# UDAWA_Gadadar.net
KiCad netlist of a schematic drawn in EAGLE
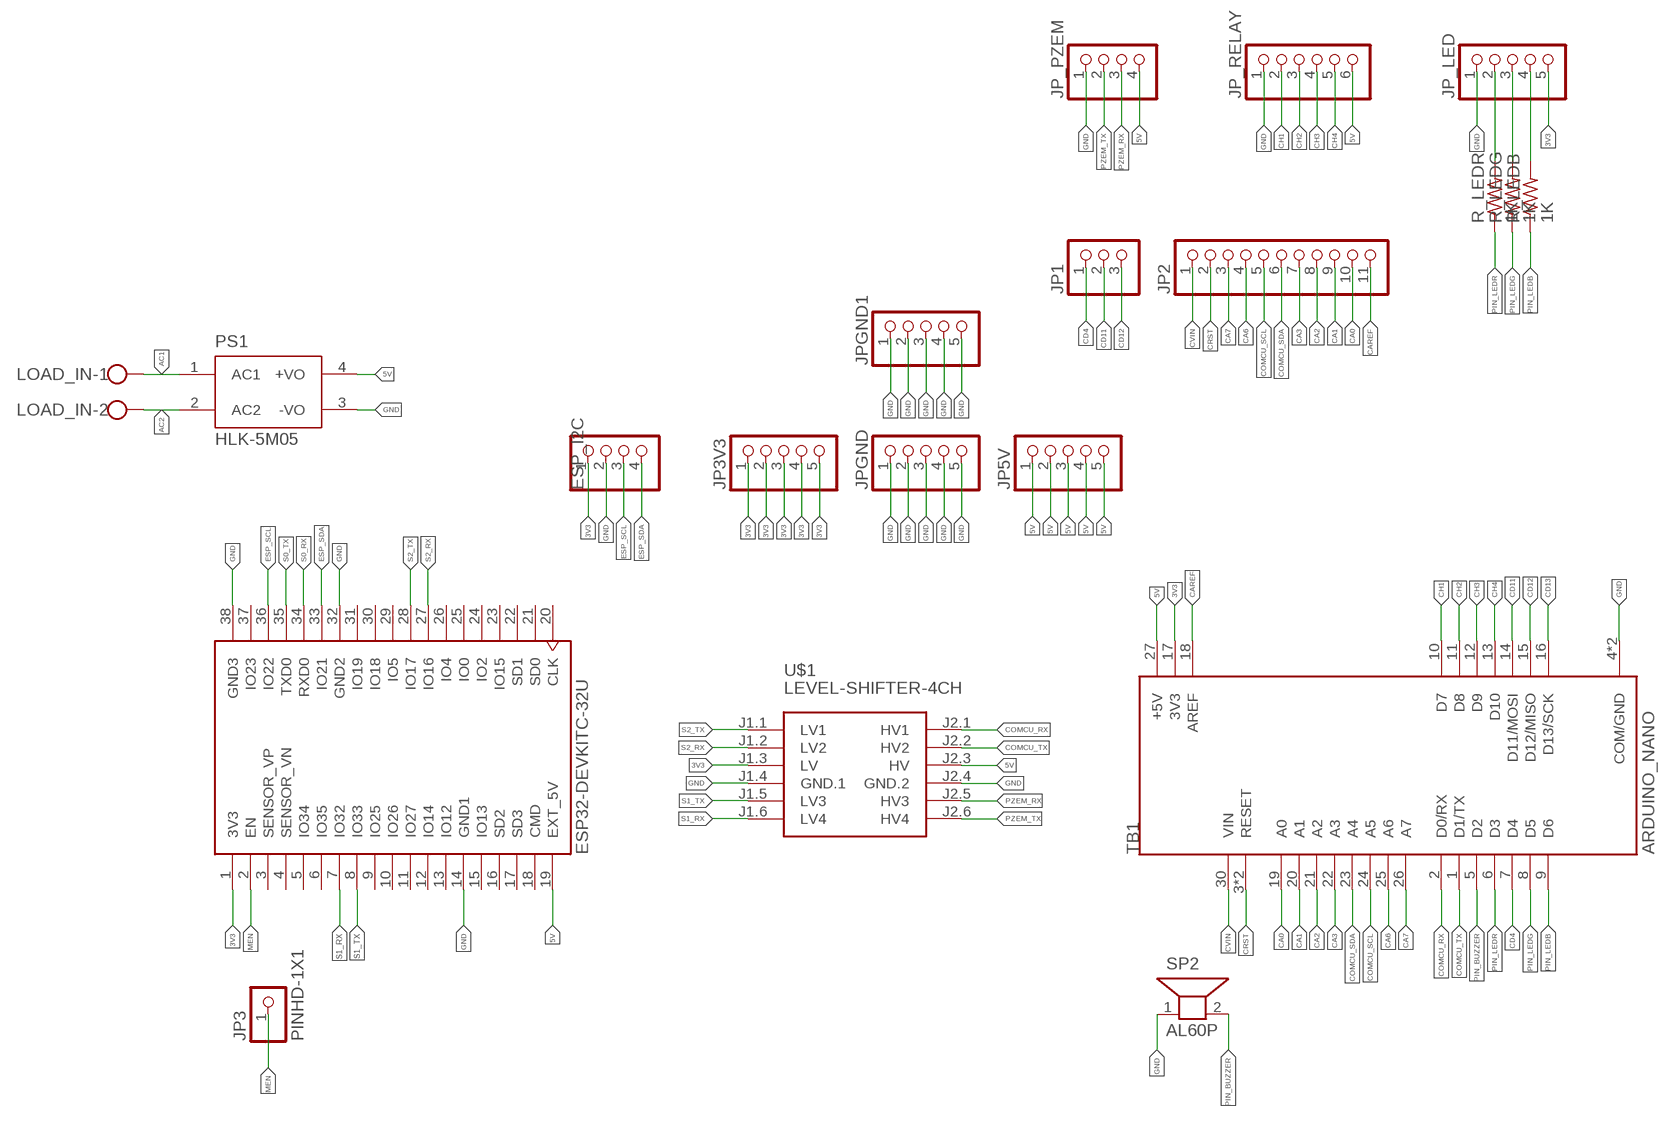
[diagram p0: schematic, sheet 1]

(export (version "E")
  (design (tool "Eeschema 10.0.6"))
  (components
    (comp (ref "ESP_I2C")
      (value "PINHD-1X4")
      (footprint "eagle-import:1X04")
      (libsource (lib "eagle-import") (part "PINHD-1X4"))
    )
    (comp (ref "JP1")
      (value "PINHD-1X3")
      (footprint "eagle-import:1X03")
      (libsource (lib "eagle-import") (part "PINHD-1X3"))
    )
    (comp (ref "JP2")
      (value "PINHD-1X11")
      (footprint "eagle-import:1X11")
      (libsource (lib "eagle-import") (part "PINHD-1X11"))
    )
    (comp (ref "JP3")
      (value "PINHD-1X1")
      (footprint "eagle-import:1X01")
      (libsource (lib "eagle-import") (part "PINHD-1X1"))
    )
    (comp (ref "JP3V3")
      (value "PINHD-1X5")
      (footprint "eagle-import:1X05")
      (libsource (lib "eagle-import") (part "PINHD-1X5"))
    )
    (comp (ref "JP5V")
      (value "PINHD-1X5")
      (footprint "eagle-import:1X05")
      (libsource (lib "eagle-import") (part "PINHD-1X5"))
    )
    (comp (ref "JPGND")
      (value "PINHD-1X5")
      (footprint "eagle-import:1X05")
      (libsource (lib "eagle-import") (part "PINHD-1X5"))
    )
    (comp (ref "JPGND1")
      (value "PINHD-1X5")
      (footprint "eagle-import:1X05")
      (libsource (lib "eagle-import") (part "PINHD-1X5"))
    )
    (comp (ref "JP_LED")
      (value "PINHD-1X5")
      (footprint "eagle-import:1X05")
      (libsource (lib "eagle-import") (part "PINHD-1X5"))
    )
    (comp (ref "JP_PZEM")
      (value "PINHD-1X4")
      (footprint "eagle-import:1X04")
      (libsource (lib "eagle-import") (part "PINHD-1X4"))
    )
    (comp (ref "JP_RELAY")
      (value "PINHD-1X6")
      (footprint "eagle-import:1X06")
      (libsource (lib "eagle-import") (part "PINHD-1X6"))
    )
    (comp (ref "LOAD_IN")
      (value "W237-102")
      (footprint "eagle-import:W237-102")
      (fields (field (name "MPN") "237-102"))
      (libsource (lib "eagle-import") (part "W237-102"))
    )
    (comp (ref "PS1")
      (value "HLK-5M05")
      (footprint "eagle-import:CONV_HLK-5M05")
      (fields (field (name "MF") "Hi-link"))
      (libsource (lib "eagle-import") (part "HLK-5M05"))
    )
    (comp (ref "R_LEDB")
      (value "1K")
      (footprint "eagle-import:0204_5")
      (libsource (lib "eagle-import") (part "R-US_0204/5"))
    )
    (comp (ref "R_LEDG")
      (value "1K")
      (footprint "eagle-import:0204_5")
      (libsource (lib "eagle-import") (part "R-US_0204/5"))
    )
    (comp (ref "R_LEDR")
      (value "1K")
      (footprint "eagle-import:0204_5")
      (libsource (lib "eagle-import") (part "R-US_0204/5"))
    )
    (comp (ref "SP2")
      (value "AL60P")
      (footprint "eagle-import:AL60P")
      (libsource (lib "eagle-import") (part "AL60P"))
    )
    (comp (ref "TB1")
      (value "ARDUINO_NANO")
      (footprint "eagle-import:SHIELD_ARDUINO_NANO")
      (fields (field (name "MF") "Arduino") (field (name "MP") "Arduino Nano"))
      (libsource (lib "eagle-import") (part "ARDUINO_NANO"))
    )
    (comp (ref "U$1")
      (value "LEVEL-SHIFTER-4CH")
      (footprint "eagle-import:LEVEL-SHIFTER-4CH")
      (libsource (lib "eagle-import") (part "LEVEL-SHIFTER-4CH"))
    )
    (comp (ref "U2")
      (value "ESP32-DEVKITC-32U")
      (footprint "eagle-import:MODULE_ESP32-DEVKITC-32U")
      (fields (field (name "MF") "Espressif Systems"))
      (libsource (lib "eagle-import") (part "ESP32-DEVKITC-32U"))
    )
  )
  (nets
    (net (code "1") (name "3V3") (class "Default")
      (node (ref "ESP_I2C") (pin "1") (pinfunction "1_1") (pintype "passive"))
      (node (ref "JP3V3") (pin "1") (pinfunction "1_1") (pintype "passive"))
      (node (ref "JP3V3") (pin "2") (pinfunction "2_2") (pintype "passive"))
      (node (ref "JP3V3") (pin "3") (pinfunction "3_3") (pintype "passive"))
      (node (ref "JP3V3") (pin "4") (pinfunction "4_4") (pintype "passive"))
      (node (ref "JP3V3") (pin "5") (pinfunction "5_5") (pintype "passive"))
      (node (ref "JP_LED") (pin "5") (pinfunction "5_5") (pintype "passive"))
      (node (ref "TB1") (pin "17") (pinfunction "3V3_17") (pintype "power_in"))
      (node (ref "U$1") (pin "J1.3") (pinfunction "LV_J1.3") (pintype "power_in"))
      (node (ref "U2") (pin "1") (pinfunction "3V3_1") (pintype "power_in"))
    )
    (net (code "2") (name "5V") (class "Default")
      (node (ref "JP5V") (pin "1") (pinfunction "1_1") (pintype "passive"))
      (node (ref "JP5V") (pin "2") (pinfunction "2_2") (pintype "passive"))
      (node (ref "JP5V") (pin "3") (pinfunction "3_3") (pintype "passive"))
      (node (ref "JP5V") (pin "4") (pinfunction "4_4") (pintype "passive"))
      (node (ref "JP5V") (pin "5") (pinfunction "5_5") (pintype "passive"))
      (node (ref "JP_PZEM") (pin "4") (pinfunction "4_4") (pintype "passive"))
      (node (ref "JP_RELAY") (pin "6") (pinfunction "6_6") (pintype "passive"))
      (node (ref "PS1") (pin "4") (pinfunction "+VO_4") (pintype "output"))
      (node (ref "TB1") (pin "27") (pinfunction "+5V_27") (pintype "power_in"))
      (node (ref "U$1") (pin "J2.3") (pinfunction "HV_J2.3") (pintype "power_in"))
      (node (ref "U2") (pin "19") (pinfunction "EXT_5V_19") (pintype "power_in"))
    )
    (net (code "3") (name "AC1") (class "Default")
      (node (ref "LOAD_IN") (pin "1") (pinfunction "KL_1") (pintype "passive"))
      (node (ref "PS1") (pin "1") (pinfunction "AC1_1") (pintype "input"))
    )
    (net (code "4") (name "AC2") (class "Default")
      (node (ref "LOAD_IN") (pin "2") (pinfunction "KL_2") (pintype "passive"))
      (node (ref "PS1") (pin "2") (pinfunction "AC2_2") (pintype "input"))
    )
    (net (code "5") (name "CA0") (class "Default")
      (node (ref "JP2") (pin "10") (pinfunction "10_10") (pintype "passive"))
      (node (ref "TB1") (pin "19") (pinfunction "A0_19") (pintype "input"))
    )
    (net (code "6") (name "CA1") (class "Default")
      (node (ref "JP2") (pin "9") (pinfunction "9_9") (pintype "passive"))
      (node (ref "TB1") (pin "20") (pinfunction "A1_20") (pintype "input"))
    )
    (net (code "7") (name "CA2") (class "Default")
      (node (ref "JP2") (pin "8") (pinfunction "8_8") (pintype "passive"))
      (node (ref "TB1") (pin "21") (pinfunction "A2_21") (pintype "input"))
    )
    (net (code "8") (name "CA3") (class "Default")
      (node (ref "JP2") (pin "7") (pinfunction "7_7") (pintype "passive"))
      (node (ref "TB1") (pin "22") (pinfunction "A3_22") (pintype "input"))
    )
    (net (code "9") (name "CA6") (class "Default")
      (node (ref "JP2") (pin "4") (pinfunction "4_4") (pintype "passive"))
      (node (ref "TB1") (pin "25") (pinfunction "A6_25") (pintype "input"))
    )
    (net (code "10") (name "CA7") (class "Default")
      (node (ref "JP2") (pin "3") (pinfunction "3_3") (pintype "passive"))
      (node (ref "TB1") (pin "26") (pinfunction "A7_26") (pintype "input"))
    )
    (net (code "11") (name "CAREF") (class "Default")
      (node (ref "JP2") (pin "11") (pinfunction "11_11") (pintype "passive"))
      (node (ref "TB1") (pin "18") (pinfunction "AREF_18") (pintype "power_in"))
    )
    (net (code "12") (name "CD4") (class "Default")
      (node (ref "JP1") (pin "1") (pinfunction "1_1") (pintype "passive"))
      (node (ref "TB1") (pin "7") (pinfunction "D4_7") (pintype "bidirectional"))
    )
    (net (code "13") (name "CD11") (class "Default")
      (node (ref "JP1") (pin "2") (pinfunction "2_2") (pintype "passive"))
      (node (ref "TB1") (pin "14") (pinfunction "D11/MOSI_14") (pintype "bidirectional"))
    )
    (net (code "14") (name "CD12") (class "Default")
      (node (ref "JP1") (pin "3") (pinfunction "3_3") (pintype "passive"))
      (node (ref "TB1") (pin "15") (pinfunction "D12/MISO_15") (pintype "bidirectional"))
    )
    (net (code "15") (name "CD13") (class "Default")
      (node (ref "TB1") (pin "16") (pinfunction "D13/SCK_16") (pintype "bidirectional"))
    )
    (net (code "16") (name "CH1") (class "Default")
      (node (ref "JP_RELAY") (pin "2") (pinfunction "2_2") (pintype "passive"))
      (node (ref "TB1") (pin "10") (pinfunction "D7_10") (pintype "bidirectional"))
    )
    (net (code "17") (name "CH2") (class "Default")
      (node (ref "JP_RELAY") (pin "3") (pinfunction "3_3") (pintype "passive"))
      (node (ref "TB1") (pin "11") (pinfunction "D8_11") (pintype "bidirectional"))
    )
    (net (code "18") (name "CH3") (class "Default")
      (node (ref "JP_RELAY") (pin "4") (pinfunction "4_4") (pintype "passive"))
      (node (ref "TB1") (pin "12") (pinfunction "D9_12") (pintype "bidirectional"))
    )
    (net (code "19") (name "CH4") (class "Default")
      (node (ref "JP_RELAY") (pin "5") (pinfunction "5_5") (pintype "passive"))
      (node (ref "TB1") (pin "13") (pinfunction "D10_13") (pintype "bidirectional"))
    )
    (net (code "20") (name "COMCU_RX") (class "Default")
      (node (ref "TB1") (pin "2") (pinfunction "D0/RX_2") (pintype "bidirectional"))
      (node (ref "U$1") (pin "J2.1") (pinfunction "HV1_J2.1") (pintype "bidirectional"))
    )
    (net (code "21") (name "COMCU_SCL") (class "Default")
      (node (ref "JP2") (pin "5") (pinfunction "5_5") (pintype "passive"))
      (node (ref "TB1") (pin "24") (pinfunction "A5_24") (pintype "input"))
    )
    (net (code "22") (name "COMCU_SDA") (class "Default")
      (node (ref "JP2") (pin "6") (pinfunction "6_6") (pintype "passive"))
      (node (ref "TB1") (pin "23") (pinfunction "A4_23") (pintype "input"))
    )
    (net (code "23") (name "COMCU_TX") (class "Default")
      (node (ref "TB1") (pin "1") (pinfunction "D1/TX_1") (pintype "bidirectional"))
      (node (ref "U$1") (pin "J2.2") (pinfunction "HV2_J2.2") (pintype "bidirectional"))
    )
    (net (code "24") (name "CRST") (class "Default")
      (node (ref "JP2") (pin "2") (pinfunction "2_2") (pintype "passive"))
      (node (ref "TB1") (pin "28") (pinfunction "RESET_28") (pintype "input"))
      (node (ref "TB1") (pin "3") (pinfunction "RESET_3") (pintype "input"))
    )
    (net (code "25") (name "CVIN") (class "Default")
      (node (ref "JP2") (pin "1") (pinfunction "1_1") (pintype "passive"))
      (node (ref "TB1") (pin "30") (pinfunction "VIN_30") (pintype "input"))
    )
    (net (code "26") (name "ESP_SCL") (class "Default")
      (node (ref "ESP_I2C") (pin "3") (pinfunction "3_3") (pintype "passive"))
      (node (ref "U2") (pin "36") (pinfunction "IO22_36") (pintype "bidirectional"))
    )
    (net (code "27") (name "ESP_SDA") (class "Default")
      (node (ref "ESP_I2C") (pin "4") (pinfunction "4_4") (pintype "passive"))
      (node (ref "U2") (pin "33") (pinfunction "IO21_33") (pintype "bidirectional"))
    )
    (net (code "28") (name "GND") (class "Default")
      (node (ref "ESP_I2C") (pin "2") (pinfunction "2_2") (pintype "passive"))
      (node (ref "JPGND") (pin "1") (pinfunction "1_1") (pintype "passive"))
      (node (ref "JPGND") (pin "2") (pinfunction "2_2") (pintype "passive"))
      (node (ref "JPGND") (pin "3") (pinfunction "3_3") (pintype "passive"))
      (node (ref "JPGND") (pin "4") (pinfunction "4_4") (pintype "passive"))
      (node (ref "JPGND") (pin "5") (pinfunction "5_5") (pintype "passive"))
      (node (ref "JPGND1") (pin "1") (pinfunction "1_1") (pintype "passive"))
      (node (ref "JPGND1") (pin "2") (pinfunction "2_2") (pintype "passive"))
      (node (ref "JPGND1") (pin "3") (pinfunction "3_3") (pintype "passive"))
      (node (ref "JPGND1") (pin "4") (pinfunction "4_4") (pintype "passive"))
      (node (ref "JPGND1") (pin "5") (pinfunction "5_5") (pintype "passive"))
      (node (ref "JP_LED") (pin "1") (pinfunction "1_1") (pintype "passive"))
      (node (ref "JP_PZEM") (pin "1") (pinfunction "1_1") (pintype "passive"))
      (node (ref "JP_RELAY") (pin "1") (pinfunction "1_1") (pintype "passive"))
      (node (ref "PS1") (pin "3") (pinfunction "-VO_3") (pintype "output"))
      (node (ref "SP2") (pin "1") (pinfunction "1_1") (pintype "passive"))
      (node (ref "TB1") (pin "29") (pinfunction "COM/GND_29") (pintype "power_in"))
      (node (ref "TB1") (pin "4") (pinfunction "COM/GND_4") (pintype "power_in"))
      (node (ref "U$1") (pin "J1.4") (pinfunction "GND.1_J1.4") (pintype "power_in"))
      (node (ref "U$1") (pin "J2.4") (pinfunction "GND.2_J2.4") (pintype "power_in"))
      (node (ref "U2") (pin "14") (pinfunction "GND1_14") (pintype "power_in"))
      (node (ref "U2") (pin "32") (pinfunction "GND2_32") (pintype "power_in"))
      (node (ref "U2") (pin "38") (pinfunction "GND3_38") (pintype "power_in"))
    )
    (net (code "29") (name "MEN") (class "Default")
      (node (ref "JP3") (pin "1") (pinfunction "1_1") (pintype "passive"))
      (node (ref "U2") (pin "2") (pinfunction "EN_2") (pintype "input"))
    )
    (net (code "30") (name "Net-(JP_LED-Pad2)") (class "Default")
      (node (ref "JP_LED") (pin "2") (pinfunction "2_2") (pintype "passive"))
      (node (ref "R_LEDR") (pin "2") (pinfunction "2_2") (pintype "passive"))
    )
    (net (code "31") (name "Net-(JP_LED-Pad3)") (class "Default")
      (node (ref "JP_LED") (pin "3") (pinfunction "3_3") (pintype "passive"))
      (node (ref "R_LEDG") (pin "2") (pinfunction "2_2") (pintype "passive"))
    )
    (net (code "32") (name "Net-(JP_LED-Pad4)") (class "Default")
      (node (ref "JP_LED") (pin "4") (pinfunction "4_4") (pintype "passive"))
      (node (ref "R_LEDB") (pin "2") (pinfunction "2_2") (pintype "passive"))
    )
    (net (code "33") (name "PIN_BUZZER") (class "Default")
      (node (ref "SP2") (pin "2") (pinfunction "2_2") (pintype "passive"))
      (node (ref "TB1") (pin "5") (pinfunction "D2_5") (pintype "bidirectional"))
    )
    (net (code "34") (name "PIN_LEDB") (class "Default")
      (node (ref "R_LEDB") (pin "1") (pinfunction "1_1") (pintype "passive"))
      (node (ref "TB1") (pin "9") (pinfunction "D6_9") (pintype "bidirectional"))
    )
    (net (code "35") (name "PIN_LEDG") (class "Default")
      (node (ref "R_LEDG") (pin "1") (pinfunction "1_1") (pintype "passive"))
      (node (ref "TB1") (pin "8") (pinfunction "D5_8") (pintype "bidirectional"))
    )
    (net (code "36") (name "PIN_LEDR") (class "Default")
      (node (ref "R_LEDR") (pin "1") (pinfunction "1_1") (pintype "passive"))
      (node (ref "TB1") (pin "6") (pinfunction "D3_6") (pintype "bidirectional"))
    )
    (net (code "37") (name "PZEM_RX") (class "Default")
      (node (ref "JP_PZEM") (pin "3") (pinfunction "3_3") (pintype "passive"))
      (node (ref "U$1") (pin "J2.5") (pinfunction "HV3_J2.5") (pintype "bidirectional"))
    )
    (net (code "38") (name "PZEM_TX") (class "Default")
      (node (ref "JP_PZEM") (pin "2") (pinfunction "2_2") (pintype "passive"))
      (node (ref "U$1") (pin "J2.6") (pinfunction "HV4_J2.6") (pintype "bidirectional"))
    )
    (net (code "39") (name "S0_RX") (class "Default")
      (node (ref "U2") (pin "34") (pinfunction "RXD0_34") (pintype "input"))
    )
    (net (code "40") (name "S0_TX") (class "Default")
      (node (ref "U2") (pin "35") (pinfunction "TXD0_35") (pintype "output"))
    )
    (net (code "41") (name "S1_RX") (class "Default")
      (node (ref "U$1") (pin "J1.6") (pinfunction "LV4_J1.6") (pintype "bidirectional"))
      (node (ref "U2") (pin "7") (pinfunction "IO32_7") (pintype "bidirectional"))
    )
    (net (code "42") (name "S1_TX") (class "Default")
      (node (ref "U$1") (pin "J1.5") (pinfunction "LV3_J1.5") (pintype "bidirectional"))
      (node (ref "U2") (pin "8") (pinfunction "IO33_8") (pintype "bidirectional"))
    )
    (net (code "43") (name "S2_RX") (class "Default")
      (node (ref "U$1") (pin "J1.2") (pinfunction "LV2_J1.2") (pintype "bidirectional"))
      (node (ref "U2") (pin "27") (pinfunction "IO16_27") (pintype "bidirectional"))
    )
    (net (code "44") (name "S2_TX") (class "Default")
      (node (ref "U$1") (pin "J1.1") (pinfunction "LV1_J1.1") (pintype "bidirectional"))
      (node (ref "U2") (pin "28") (pinfunction "IO17_28") (pintype "bidirectional"))
    )
    (net (code "45") (name "unconnected-(U2-CLK-Pad20)") (class "Default")
      (node (ref "U2") (pin "20") (pinfunction "CLK_20") (pintype "input"))
    )
    (net (code "46") (name "unconnected-(U2-CMD-Pad18)") (class "Default")
      (node (ref "U2") (pin "18") (pinfunction "CMD_18") (pintype "bidirectional"))
    )
    (net (code "47") (name "unconnected-(U2-IO0-Pad25)") (class "Default")
      (node (ref "U2") (pin "25") (pinfunction "IO0_25") (pintype "bidirectional"))
    )
    (net (code "48") (name "unconnected-(U2-IO2-Pad24)") (class "Default")
      (node (ref "U2") (pin "24") (pinfunction "IO2_24") (pintype "bidirectional"))
    )
    (net (code "49") (name "unconnected-(U2-IO4-Pad26)") (class "Default")
      (node (ref "U2") (pin "26") (pinfunction "IO4_26") (pintype "bidirectional"))
    )
    (net (code "50") (name "unconnected-(U2-IO5-Pad29)") (class "Default")
      (node (ref "U2") (pin "29") (pinfunction "IO5_29") (pintype "bidirectional"))
    )
    (net (code "51") (name "unconnected-(U2-IO12-Pad13)") (class "Default")
      (node (ref "U2") (pin "13") (pinfunction "IO12_13") (pintype "bidirectional"))
    )
    (net (code "52") (name "unconnected-(U2-IO13-Pad15)") (class "Default")
      (node (ref "U2") (pin "15") (pinfunction "IO13_15") (pintype "bidirectional"))
    )
    (net (code "53") (name "unconnected-(U2-IO14-Pad12)") (class "Default")
      (node (ref "U2") (pin "12") (pinfunction "IO14_12") (pintype "bidirectional"))
    )
    (net (code "54") (name "unconnected-(U2-IO15-Pad23)") (class "Default")
      (node (ref "U2") (pin "23") (pinfunction "IO15_23") (pintype "bidirectional"))
    )
    (net (code "55") (name "unconnected-(U2-IO18-Pad30)") (class "Default")
      (node (ref "U2") (pin "30") (pinfunction "IO18_30") (pintype "bidirectional"))
    )
    (net (code "56") (name "unconnected-(U2-IO19-Pad31)") (class "Default")
      (node (ref "U2") (pin "31") (pinfunction "IO19_31") (pintype "bidirectional"))
    )
    (net (code "57") (name "unconnected-(U2-IO23-Pad37)") (class "Default")
      (node (ref "U2") (pin "37") (pinfunction "IO23_37") (pintype "bidirectional"))
    )
    (net (code "58") (name "unconnected-(U2-IO25-Pad9)") (class "Default")
      (node (ref "U2") (pin "9") (pinfunction "IO25_9") (pintype "bidirectional"))
    )
    (net (code "59") (name "unconnected-(U2-IO26-Pad10)") (class "Default")
      (node (ref "U2") (pin "10") (pinfunction "IO26_10") (pintype "bidirectional"))
    )
    (net (code "60") (name "unconnected-(U2-IO27-Pad11)") (class "Default")
      (node (ref "U2") (pin "11") (pinfunction "IO27_11") (pintype "bidirectional"))
    )
    (net (code "61") (name "unconnected-(U2-IO34-Pad5)") (class "Default")
      (node (ref "U2") (pin "5") (pinfunction "IO34_5") (pintype "bidirectional"))
    )
    (net (code "62") (name "unconnected-(U2-IO35-Pad6)") (class "Default")
      (node (ref "U2") (pin "6") (pinfunction "IO35_6") (pintype "bidirectional"))
    )
    (net (code "63") (name "unconnected-(U2-SD0-Pad21)") (class "Default")
      (node (ref "U2") (pin "21") (pinfunction "SD0_21") (pintype "bidirectional"))
    )
    (net (code "64") (name "unconnected-(U2-SD1-Pad22)") (class "Default")
      (node (ref "U2") (pin "22") (pinfunction "SD1_22") (pintype "bidirectional"))
    )
    (net (code "65") (name "unconnected-(U2-SD2-Pad16)") (class "Default")
      (node (ref "U2") (pin "16") (pinfunction "SD2_16") (pintype "bidirectional"))
    )
    (net (code "66") (name "unconnected-(U2-SD3-Pad17)") (class "Default")
      (node (ref "U2") (pin "17") (pinfunction "SD3_17") (pintype "bidirectional"))
    )
    (net (code "67") (name "unconnected-(U2-SENSOR_VN-Pad4)") (class "Default")
      (node (ref "U2") (pin "4") (pinfunction "SENSOR_VN_4") (pintype "input"))
    )
    (net (code "68") (name "unconnected-(U2-SENSOR_VP-Pad3)") (class "Default")
      (node (ref "U2") (pin "3") (pinfunction "SENSOR_VP_3") (pintype "input"))
    )
  )
)
